# Peripherals.net
KiCad netlist of a schematic drawn in Altium Designer
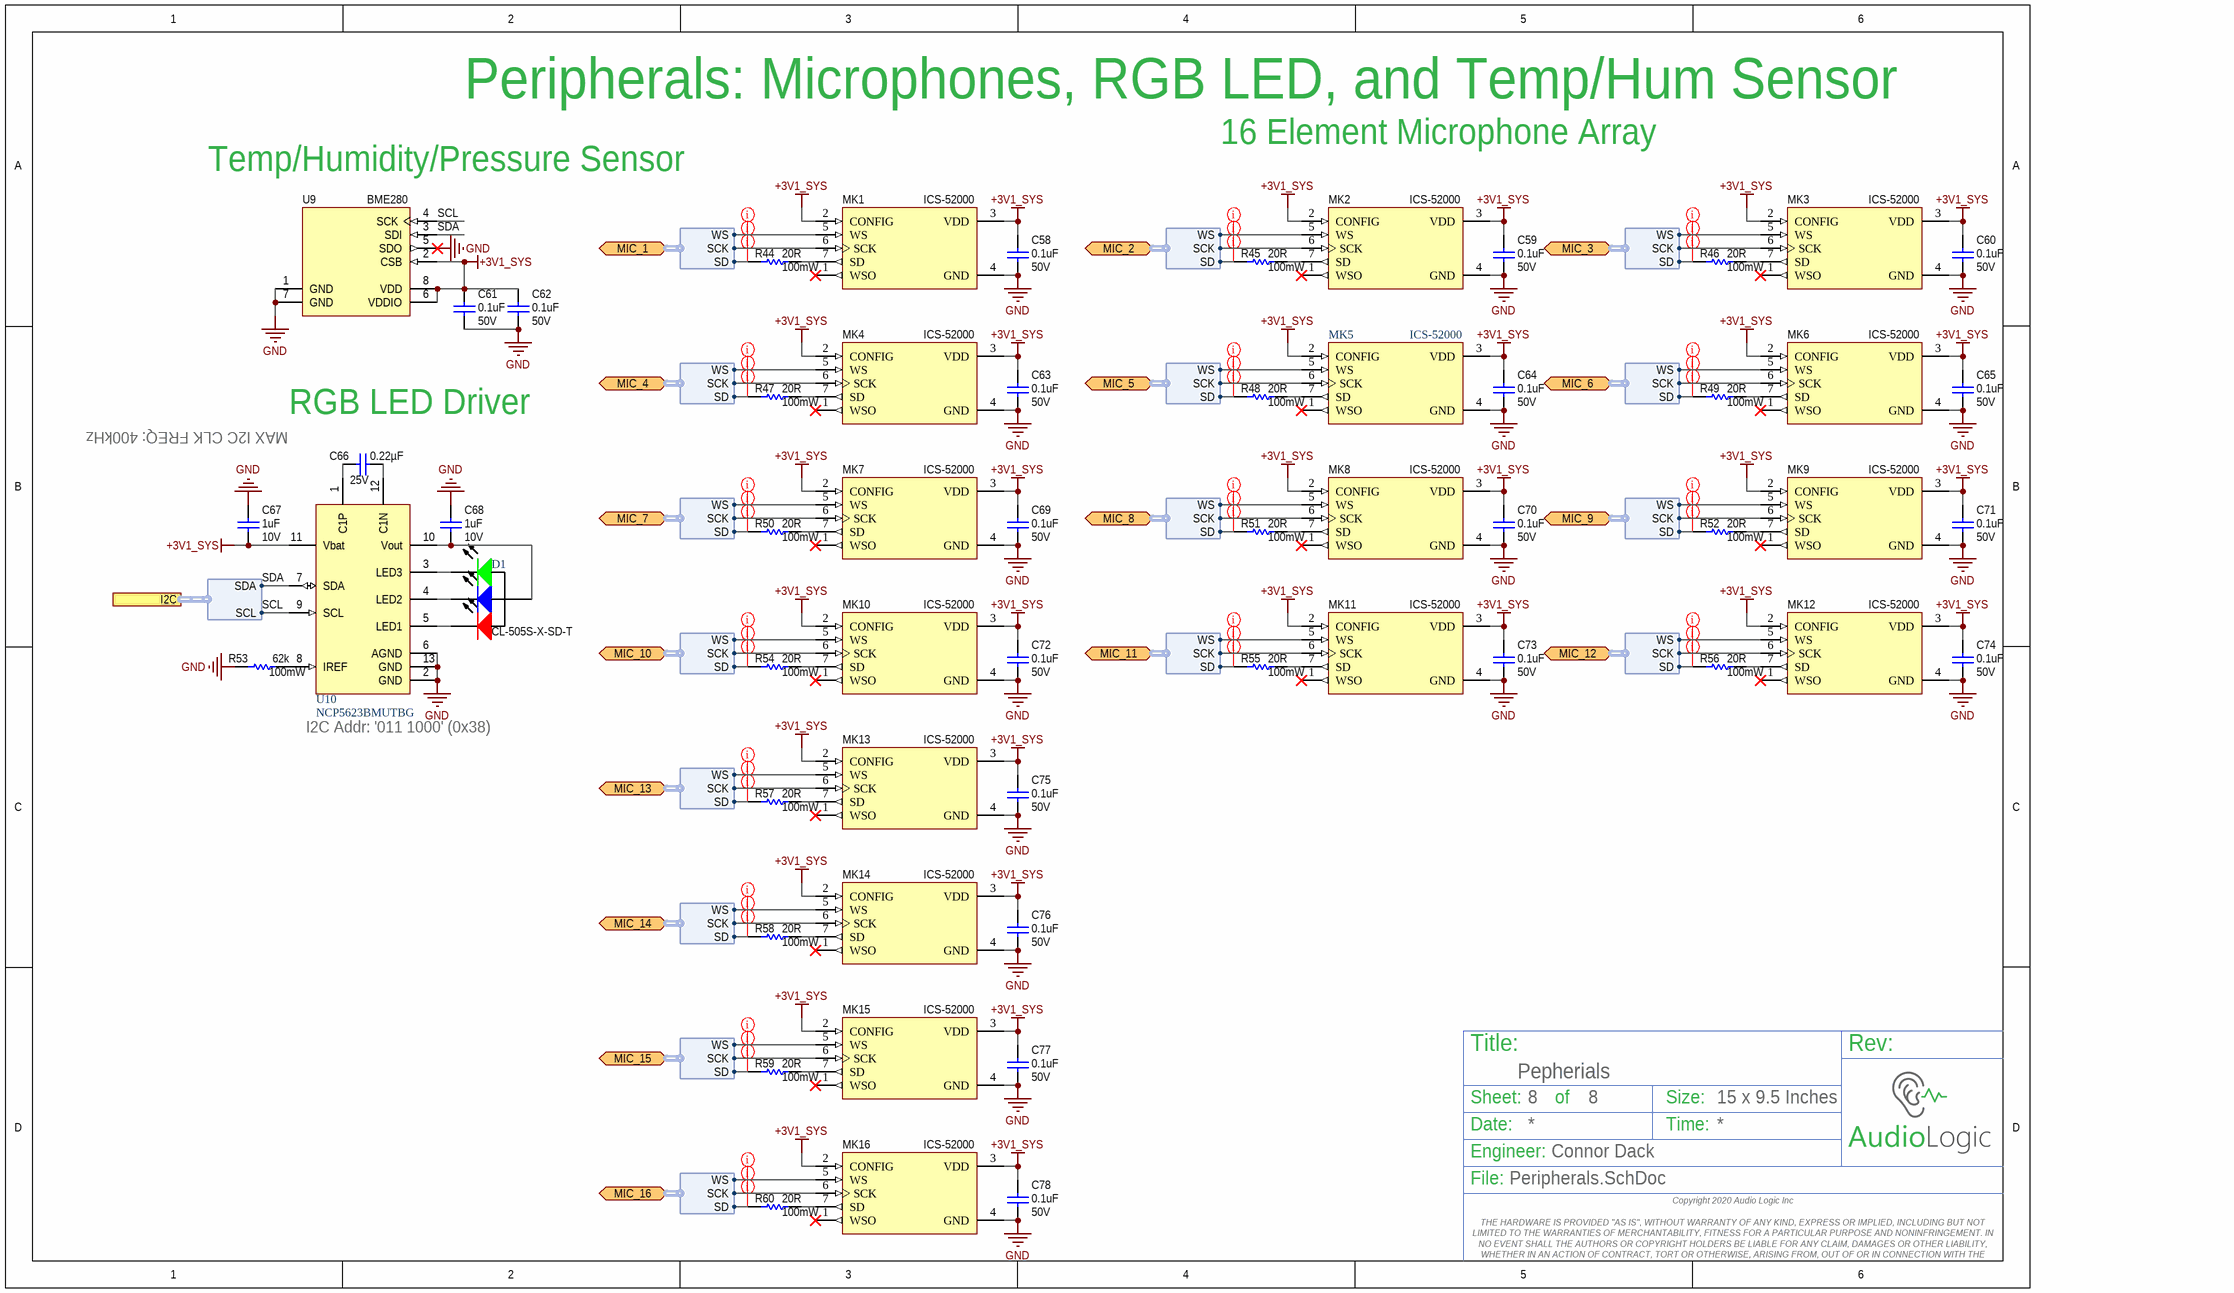
[diagram p0: Peripherals.SchDoc]

(export (version "E")
  (design (tool "Eeschema 10.0.6"))
  (components
    (comp (ref "C58")
      (value "UMK105B7104KVHF")
      (footprint "2-0402_L")
      (description "CAP CER 0.1uF 50V X7R +/-10% 0402 AEC-Q200")
      (fields
        (field (name "MANUFACTURER") "Taiyo Yuden")
        (field (name "TOLERANCE") "10%")
        (field (name "CAPACITANCE") "0.1uF")
        (field (name "VOLTAGE RATING") "50V")
      )
      (libsource (lib "Schematic_Components") (part "UMK105B7104KVHF"))
    )
    (comp (ref "C59")
      (value "UMK105B7104KVHF")
      (footprint "2-0402_L")
      (description "CAP CER 0.1uF 50V X7R +/-10% 0402 AEC-Q200")
      (fields
        (field (name "MANUFACTURER") "Taiyo Yuden")
        (field (name "TOLERANCE") "10%")
        (field (name "CAPACITANCE") "0.1uF")
        (field (name "VOLTAGE RATING") "50V")
      )
      (libsource (lib "Schematic_Components") (part "UMK105B7104KVHF"))
    )
    (comp (ref "C60")
      (value "UMK105B7104KVHF")
      (footprint "2-0402_L")
      (description "CAP CER 0.1uF 50V X7R +/-10% 0402 AEC-Q200")
      (fields
        (field (name "MANUFACTURER") "Taiyo Yuden")
        (field (name "TOLERANCE") "10%")
        (field (name "CAPACITANCE") "0.1uF")
        (field (name "VOLTAGE RATING") "50V")
      )
      (libsource (lib "Schematic_Components") (part "UMK105B7104KVHF"))
    )
    (comp (ref "C61")
      (value "UMK105B7104KVHF")
      (footprint "2-0402_L")
      (description "CAP CER 0.1uF 50V X7R +/-10% 0402 AEC-Q200")
      (fields
        (field (name "MANUFACTURER") "Taiyo Yuden")
        (field (name "TOLERANCE") "10%")
        (field (name "CAPACITANCE") "0.1uF")
        (field (name "VOLTAGE RATING") "50V")
      )
      (libsource (lib "Schematic_Components") (part "UMK105B7104KVHF"))
    )
    (comp (ref "C62")
      (value "UMK105B7104KVHF")
      (footprint "2-0402_L")
      (description "CAP CER 0.1uF 50V X7R +/-10% 0402 AEC-Q200")
      (fields
        (field (name "MANUFACTURER") "Taiyo Yuden")
        (field (name "TOLERANCE") "10%")
        (field (name "CAPACITANCE") "0.1uF")
        (field (name "VOLTAGE RATING") "50V")
      )
      (libsource (lib "Schematic_Components") (part "UMK105B7104KVHF"))
    )
    (comp (ref "C63")
      (value "UMK105B7104KVHF")
      (footprint "2-0402_L")
      (description "CAP CER 0.1uF 50V X7R +/-10% 0402 AEC-Q200")
      (fields
        (field (name "MANUFACTURER") "Taiyo Yuden")
        (field (name "TOLERANCE") "10%")
        (field (name "CAPACITANCE") "0.1uF")
        (field (name "VOLTAGE RATING") "50V")
      )
      (libsource (lib "Schematic_Components") (part "UMK105B7104KVHF"))
    )
    (comp (ref "C64")
      (value "UMK105B7104KVHF")
      (footprint "2-0402_L")
      (description "CAP CER 0.1uF 50V X7R +/-10% 0402 AEC-Q200")
      (fields
        (field (name "MANUFACTURER") "Taiyo Yuden")
        (field (name "TOLERANCE") "10%")
        (field (name "CAPACITANCE") "0.1uF")
        (field (name "VOLTAGE RATING") "50V")
      )
      (libsource (lib "Schematic_Components") (part "UMK105B7104KVHF"))
    )
    (comp (ref "C65")
      (value "UMK105B7104KVHF")
      (footprint "2-0402_L")
      (description "CAP CER 0.1uF 50V X7R +/-10% 0402 AEC-Q200")
      (fields
        (field (name "MANUFACTURER") "Taiyo Yuden")
        (field (name "TOLERANCE") "10%")
        (field (name "CAPACITANCE") "0.1uF")
        (field (name "VOLTAGE RATING") "50V")
      )
      (libsource (lib "Schematic_Components") (part "UMK105B7104KVHF"))
    )
    (comp (ref "C66")
      (value "C1005X7R1E224K050BB")
      (footprint "2-0402_L")
      (description "CAP CER 0.22UF 25V X7R 0402")
      (fields
        (field (name "MANUFACTURER") "TDK Corporation")
        (field (name "TOLERANCE") "±10%")
        (field (name "VOLTAGE - RATED") "25V")
        (field (name "CAPACITANCE") "0.22µF")
      )
      (libsource (lib "Schematic_Components") (part "C1005X7R1E224K050BB"))
    )
    (comp (ref "C67")
      (value "CGB2A1X5R1A105K033BC")
      (footprint "2-0402_L")
      (description "CAP CER 1UF 10V X5R 0402")
      (fields
        (field (name "MANUFACTURER") "TDK")
        (field (name "TOLERANCE") "10%")
        (field (name "VOLTAGE RATING") "10V")
        (field (name "CAPACITANCE") "1uF")
      )
      (libsource (lib "Schematic_Components") (part "CGB2A1X5R1A105K033BC"))
    )
    (comp (ref "C68")
      (value "CGB2A1X5R1A105K033BC")
      (footprint "2-0402_L")
      (description "CAP CER 1UF 10V X5R 0402")
      (fields
        (field (name "MANUFACTURER") "TDK")
        (field (name "TOLERANCE") "10%")
        (field (name "VOLTAGE RATING") "10V")
        (field (name "CAPACITANCE") "1uF")
      )
      (libsource (lib "Schematic_Components") (part "CGB2A1X5R1A105K033BC"))
    )
    (comp (ref "C69")
      (value "UMK105B7104KVHF")
      (footprint "2-0402_L")
      (description "CAP CER 0.1uF 50V X7R +/-10% 0402 AEC-Q200")
      (fields
        (field (name "MANUFACTURER") "Taiyo Yuden")
        (field (name "TOLERANCE") "10%")
        (field (name "CAPACITANCE") "0.1uF")
        (field (name "VOLTAGE RATING") "50V")
      )
      (libsource (lib "Schematic_Components") (part "UMK105B7104KVHF"))
    )
    (comp (ref "C70")
      (value "UMK105B7104KVHF")
      (footprint "2-0402_L")
      (description "CAP CER 0.1uF 50V X7R +/-10% 0402 AEC-Q200")
      (fields
        (field (name "MANUFACTURER") "Taiyo Yuden")
        (field (name "TOLERANCE") "10%")
        (field (name "CAPACITANCE") "0.1uF")
        (field (name "VOLTAGE RATING") "50V")
      )
      (libsource (lib "Schematic_Components") (part "UMK105B7104KVHF"))
    )
    (comp (ref "C71")
      (value "UMK105B7104KVHF")
      (footprint "2-0402_L")
      (description "CAP CER 0.1uF 50V X7R +/-10% 0402 AEC-Q200")
      (fields
        (field (name "MANUFACTURER") "Taiyo Yuden")
        (field (name "TOLERANCE") "10%")
        (field (name "CAPACITANCE") "0.1uF")
        (field (name "VOLTAGE RATING") "50V")
      )
      (libsource (lib "Schematic_Components") (part "UMK105B7104KVHF"))
    )
    (comp (ref "C72")
      (value "UMK105B7104KVHF")
      (footprint "2-0402_L")
      (description "CAP CER 0.1uF 50V X7R +/-10% 0402 AEC-Q200")
      (fields
        (field (name "MANUFACTURER") "Taiyo Yuden")
        (field (name "TOLERANCE") "10%")
        (field (name "CAPACITANCE") "0.1uF")
        (field (name "VOLTAGE RATING") "50V")
      )
      (libsource (lib "Schematic_Components") (part "UMK105B7104KVHF"))
    )
    (comp (ref "C73")
      (value "UMK105B7104KVHF")
      (footprint "2-0402_L")
      (description "CAP CER 0.1uF 50V X7R +/-10% 0402 AEC-Q200")
      (fields
        (field (name "MANUFACTURER") "Taiyo Yuden")
        (field (name "TOLERANCE") "10%")
        (field (name "CAPACITANCE") "0.1uF")
        (field (name "VOLTAGE RATING") "50V")
      )
      (libsource (lib "Schematic_Components") (part "UMK105B7104KVHF"))
    )
    (comp (ref "C74")
      (value "UMK105B7104KVHF")
      (footprint "2-0402_L")
      (description "CAP CER 0.1uF 50V X7R +/-10% 0402 AEC-Q200")
      (fields
        (field (name "MANUFACTURER") "Taiyo Yuden")
        (field (name "TOLERANCE") "10%")
        (field (name "CAPACITANCE") "0.1uF")
        (field (name "VOLTAGE RATING") "50V")
      )
      (libsource (lib "Schematic_Components") (part "UMK105B7104KVHF"))
    )
    (comp (ref "C75")
      (value "UMK105B7104KVHF")
      (footprint "2-0402_L")
      (description "CAP CER 0.1uF 50V X7R +/-10% 0402 AEC-Q200")
      (fields
        (field (name "MANUFACTURER") "Taiyo Yuden")
        (field (name "TOLERANCE") "10%")
        (field (name "CAPACITANCE") "0.1uF")
        (field (name "VOLTAGE RATING") "50V")
      )
      (libsource (lib "Schematic_Components") (part "UMK105B7104KVHF"))
    )
    (comp (ref "C76")
      (value "UMK105B7104KVHF")
      (footprint "2-0402_L")
      (description "CAP CER 0.1uF 50V X7R +/-10% 0402 AEC-Q200")
      (fields
        (field (name "MANUFACTURER") "Taiyo Yuden")
        (field (name "TOLERANCE") "10%")
        (field (name "CAPACITANCE") "0.1uF")
        (field (name "VOLTAGE RATING") "50V")
      )
      (libsource (lib "Schematic_Components") (part "UMK105B7104KVHF"))
    )
    (comp (ref "C77")
      (value "UMK105B7104KVHF")
      (footprint "2-0402_L")
      (description "CAP CER 0.1uF 50V X7R +/-10% 0402 AEC-Q200")
      (fields
        (field (name "MANUFACTURER") "Taiyo Yuden")
        (field (name "TOLERANCE") "10%")
        (field (name "CAPACITANCE") "0.1uF")
        (field (name "VOLTAGE RATING") "50V")
      )
      (libsource (lib "Schematic_Components") (part "UMK105B7104KVHF"))
    )
    (comp (ref "C78")
      (value "UMK105B7104KVHF")
      (footprint "2-0402_L")
      (description "CAP CER 0.1uF 50V X7R +/-10% 0402 AEC-Q200")
      (fields
        (field (name "MANUFACTURER") "Taiyo Yuden")
        (field (name "TOLERANCE") "10%")
        (field (name "CAPACITANCE") "0.1uF")
        (field (name "VOLTAGE RATING") "50V")
      )
      (libsource (lib "Schematic_Components") (part "UMK105B7104KVHF"))
    )
    (comp (ref "D1")
      (value "LED TRI TOP FIRING 1.0 X 1.0")
      (footprint "CL-505S")
      (fields
        (field (name "MANUFACTURER") "Citizen")
        (field (name "MANUFACTURER PART NUMBER") "CL-505S-X-SD-T")
      )
      (libsource (lib "Schematic_Components_CD") (part "CL-505S-X-SD-T"))
    )
    (comp (ref "MK1")
      (value "ICS-52000")
      (footprint "MIC_ICS-52000")
      (description "MIC MEMS DIGITAL OMNI -26DB")
      (fields (field (name "MANUFACTURER") "TDK InvenSense"))
      (libsource (lib "Schematic_Components_CD") (part "ICS-52000"))
    )
    (comp (ref "MK2")
      (value "ICS-52000")
      (footprint "MIC_ICS-52000")
      (description "MIC MEMS DIGITAL OMNI -26DB")
      (fields (field (name "MANUFACTURER") "TDK InvenSense"))
      (libsource (lib "Schematic_Components_CD") (part "ICS-52000"))
    )
    (comp (ref "MK3")
      (value "ICS-52000")
      (footprint "MIC_ICS-52000")
      (description "MIC MEMS DIGITAL OMNI -26DB")
      (fields (field (name "MANUFACTURER") "TDK InvenSense"))
      (libsource (lib "Schematic_Components_CD") (part "ICS-52000"))
    )
    (comp (ref "MK4")
      (value "ICS-52000")
      (footprint "MIC_ICS-52000")
      (description "MIC MEMS DIGITAL OMNI -26DB")
      (fields (field (name "MANUFACTURER") "TDK InvenSense"))
      (libsource (lib "Schematic_Components_CD") (part "ICS-52000"))
    )
    (comp (ref "MK5")
      (value "ICS-52000")
      (footprint "MIC_ICS-52000")
      (description "MIC MEMS DIGITAL OMNI -26DB")
      (fields (field (name "MANUFACTURER") "TDK InvenSense"))
      (libsource (lib "Schematic_Components_CD") (part "ICS-52000"))
    )
    (comp (ref "MK6")
      (value "ICS-52000")
      (footprint "MIC_ICS-52000")
      (description "MIC MEMS DIGITAL OMNI -26DB")
      (fields (field (name "MANUFACTURER") "TDK InvenSense"))
      (libsource (lib "Schematic_Components_CD") (part "ICS-52000"))
    )
    (comp (ref "MK7")
      (value "ICS-52000")
      (footprint "MIC_ICS-52000")
      (description "MIC MEMS DIGITAL OMNI -26DB")
      (fields (field (name "MANUFACTURER") "TDK InvenSense"))
      (libsource (lib "Schematic_Components_CD") (part "ICS-52000"))
    )
    (comp (ref "MK8")
      (value "ICS-52000")
      (footprint "MIC_ICS-52000")
      (description "MIC MEMS DIGITAL OMNI -26DB")
      (fields (field (name "MANUFACTURER") "TDK InvenSense"))
      (libsource (lib "Schematic_Components_CD") (part "ICS-52000"))
    )
    (comp (ref "MK9")
      (value "ICS-52000")
      (footprint "MIC_ICS-52000")
      (description "MIC MEMS DIGITAL OMNI -26DB")
      (fields (field (name "MANUFACTURER") "TDK InvenSense"))
      (libsource (lib "Schematic_Components_CD") (part "ICS-52000"))
    )
    (comp (ref "MK10")
      (value "ICS-52000")
      (footprint "MIC_ICS-52000")
      (description "MIC MEMS DIGITAL OMNI -26DB")
      (fields (field (name "MANUFACTURER") "TDK InvenSense"))
      (libsource (lib "Schematic_Components_CD") (part "ICS-52000"))
    )
    (comp (ref "MK11")
      (value "ICS-52000")
      (footprint "MIC_ICS-52000")
      (description "MIC MEMS DIGITAL OMNI -26DB")
      (fields (field (name "MANUFACTURER") "TDK InvenSense"))
      (libsource (lib "Schematic_Components_CD") (part "ICS-52000"))
    )
    (comp (ref "MK12")
      (value "ICS-52000")
      (footprint "MIC_ICS-52000")
      (description "MIC MEMS DIGITAL OMNI -26DB")
      (fields (field (name "MANUFACTURER") "TDK InvenSense"))
      (libsource (lib "Schematic_Components_CD") (part "ICS-52000"))
    )
    (comp (ref "MK13")
      (value "ICS-52000")
      (footprint "MIC_ICS-52000")
      (description "MIC MEMS DIGITAL OMNI -26DB")
      (fields (field (name "MANUFACTURER") "TDK InvenSense"))
      (libsource (lib "Schematic_Components_CD") (part "ICS-52000"))
    )
    (comp (ref "MK14")
      (value "ICS-52000")
      (footprint "MIC_ICS-52000")
      (description "MIC MEMS DIGITAL OMNI -26DB")
      (fields (field (name "MANUFACTURER") "TDK InvenSense"))
      (libsource (lib "Schematic_Components_CD") (part "ICS-52000"))
    )
    (comp (ref "MK15")
      (value "ICS-52000")
      (footprint "MIC_ICS-52000")
      (description "MIC MEMS DIGITAL OMNI -26DB")
      (fields (field (name "MANUFACTURER") "TDK InvenSense"))
      (libsource (lib "Schematic_Components_CD") (part "ICS-52000"))
    )
    (comp (ref "MK16")
      (value "ICS-52000")
      (footprint "MIC_ICS-52000")
      (description "MIC MEMS DIGITAL OMNI -26DB")
      (fields (field (name "MANUFACTURER") "TDK InvenSense"))
      (libsource (lib "Schematic_Components_CD") (part "ICS-52000"))
    )
    (comp (ref "R44")
      (value "ERJ-2RKF20R0X")
      (footprint "RESC1005X40X25LL05T05")
      (description "RES SMD 20 OHM 1% 1/10W 0402")
      (fields
        (field (name "MANUFACTURER") "Panasonic")
        (field (name "RESISTANCE") "20R")
        (field (name "POWER RATING") "100mW")
        (field (name "TOLERANCE") "1%")
      )
      (libsource (lib "Altium Content Vault") (part "RES"))
    )
    (comp (ref "R45")
      (value "ERJ-2RKF20R0X")
      (footprint "RESC1005X40X25LL05T05")
      (description "RES SMD 20 OHM 1% 1/10W 0402")
      (fields
        (field (name "MANUFACTURER") "Panasonic")
        (field (name "RESISTANCE") "20R")
        (field (name "POWER RATING") "100mW")
        (field (name "TOLERANCE") "1%")
      )
      (libsource (lib "Altium Content Vault") (part "RES"))
    )
    (comp (ref "R46")
      (value "ERJ-2RKF20R0X")
      (footprint "RESC1005X40X25LL05T05")
      (description "RES SMD 20 OHM 1% 1/10W 0402")
      (fields
        (field (name "MANUFACTURER") "Panasonic")
        (field (name "RESISTANCE") "20R")
        (field (name "POWER RATING") "100mW")
        (field (name "TOLERANCE") "1%")
      )
      (libsource (lib "Altium Content Vault") (part "RES"))
    )
    (comp (ref "R47")
      (value "ERJ-2RKF20R0X")
      (footprint "RESC1005X40X25LL05T05")
      (description "RES SMD 20 OHM 1% 1/10W 0402")
      (fields
        (field (name "MANUFACTURER") "Panasonic")
        (field (name "RESISTANCE") "20R")
        (field (name "POWER RATING") "100mW")
        (field (name "TOLERANCE") "1%")
      )
      (libsource (lib "Altium Content Vault") (part "RES"))
    )
    (comp (ref "R48")
      (value "ERJ-2RKF20R0X")
      (footprint "RESC1005X40X25LL05T05")
      (description "RES SMD 20 OHM 1% 1/10W 0402")
      (fields
        (field (name "MANUFACTURER") "Panasonic")
        (field (name "RESISTANCE") "20R")
        (field (name "POWER RATING") "100mW")
        (field (name "TOLERANCE") "1%")
      )
      (libsource (lib "Altium Content Vault") (part "RES"))
    )
    (comp (ref "R49")
      (value "ERJ-2RKF20R0X")
      (footprint "RESC1005X40X25LL05T05")
      (description "RES SMD 20 OHM 1% 1/10W 0402")
      (fields
        (field (name "MANUFACTURER") "Panasonic")
        (field (name "RESISTANCE") "20R")
        (field (name "POWER RATING") "100mW")
        (field (name "TOLERANCE") "1%")
      )
      (libsource (lib "Altium Content Vault") (part "RES"))
    )
    (comp (ref "R50")
      (value "ERJ-2RKF20R0X")
      (footprint "RESC1005X40X25LL05T05")
      (description "RES SMD 20 OHM 1% 1/10W 0402")
      (fields
        (field (name "MANUFACTURER") "Panasonic")
        (field (name "RESISTANCE") "20R")
        (field (name "POWER RATING") "100mW")
        (field (name "TOLERANCE") "1%")
      )
      (libsource (lib "Altium Content Vault") (part "RES"))
    )
    (comp (ref "R51")
      (value "ERJ-2RKF20R0X")
      (footprint "RESC1005X40X25LL05T05")
      (description "RES SMD 20 OHM 1% 1/10W 0402")
      (fields
        (field (name "MANUFACTURER") "Panasonic")
        (field (name "RESISTANCE") "20R")
        (field (name "POWER RATING") "100mW")
        (field (name "TOLERANCE") "1%")
      )
      (libsource (lib "Altium Content Vault") (part "RES"))
    )
    (comp (ref "R52")
      (value "ERJ-2RKF20R0X")
      (footprint "RESC1005X40X25LL05T05")
      (description "RES SMD 20 OHM 1% 1/10W 0402")
      (fields
        (field (name "MANUFACTURER") "Panasonic")
        (field (name "RESISTANCE") "20R")
        (field (name "POWER RATING") "100mW")
        (field (name "TOLERANCE") "1%")
      )
      (libsource (lib "Altium Content Vault") (part "RES"))
    )
    (comp (ref "R53")
      (value "ERJ-2GEJ623X")
      (footprint "2-0402_R_L")
      (description "RES SMD 62K OHM 5% 1/10W 0402")
      (fields
        (field (name "MANUFACTURER") "Panasonic Electronic Components")
        (field (name "TOLERANCE") "±5%")
        (field (name "POWER (WATTS)") "100mW")
        (field (name "RESISTANCE (OHMS)") "62k")
      )
      (libsource (lib "Schematic_Components") (part "ERJ-2GEJ623X"))
    )
    (comp (ref "R54")
      (value "ERJ-2RKF20R0X")
      (footprint "RESC1005X40X25LL05T05")
      (description "RES SMD 20 OHM 1% 1/10W 0402")
      (fields
        (field (name "MANUFACTURER") "Panasonic")
        (field (name "RESISTANCE") "20R")
        (field (name "POWER RATING") "100mW")
        (field (name "TOLERANCE") "1%")
      )
      (libsource (lib "Altium Content Vault") (part "RES"))
    )
    (comp (ref "R55")
      (value "ERJ-2RKF20R0X")
      (footprint "RESC1005X40X25LL05T05")
      (description "RES SMD 20 OHM 1% 1/10W 0402")
      (fields
        (field (name "MANUFACTURER") "Panasonic")
        (field (name "RESISTANCE") "20R")
        (field (name "POWER RATING") "100mW")
        (field (name "TOLERANCE") "1%")
      )
      (libsource (lib "Altium Content Vault") (part "RES"))
    )
    (comp (ref "R56")
      (value "ERJ-2RKF20R0X")
      (footprint "RESC1005X40X25LL05T05")
      (description "RES SMD 20 OHM 1% 1/10W 0402")
      (fields
        (field (name "MANUFACTURER") "Panasonic")
        (field (name "RESISTANCE") "20R")
        (field (name "POWER RATING") "100mW")
        (field (name "TOLERANCE") "1%")
      )
      (libsource (lib "Altium Content Vault") (part "RES"))
    )
    (comp (ref "R57")
      (value "ERJ-2RKF20R0X")
      (footprint "RESC1005X40X25LL05T05")
      (description "RES SMD 20 OHM 1% 1/10W 0402")
      (fields
        (field (name "MANUFACTURER") "Panasonic")
        (field (name "RESISTANCE") "20R")
        (field (name "POWER RATING") "100mW")
        (field (name "TOLERANCE") "1%")
      )
      (libsource (lib "Altium Content Vault") (part "RES"))
    )
    (comp (ref "R58")
      (value "ERJ-2RKF20R0X")
      (footprint "RESC1005X40X25LL05T05")
      (description "RES SMD 20 OHM 1% 1/10W 0402")
      (fields
        (field (name "MANUFACTURER") "Panasonic")
        (field (name "RESISTANCE") "20R")
        (field (name "POWER RATING") "100mW")
        (field (name "TOLERANCE") "1%")
      )
      (libsource (lib "Altium Content Vault") (part "RES"))
    )
    (comp (ref "R59")
      (value "ERJ-2RKF20R0X")
      (footprint "RESC1005X40X25LL05T05")
      (description "RES SMD 20 OHM 1% 1/10W 0402")
      (fields
        (field (name "MANUFACTURER") "Panasonic")
        (field (name "RESISTANCE") "20R")
        (field (name "POWER RATING") "100mW")
        (field (name "TOLERANCE") "1%")
      )
      (libsource (lib "Altium Content Vault") (part "RES"))
    )
    (comp (ref "R60")
      (value "ERJ-2RKF20R0X")
      (footprint "RESC1005X40X25LL05T05")
      (description "RES SMD 20 OHM 1% 1/10W 0402")
      (fields
        (field (name "MANUFACTURER") "Panasonic")
        (field (name "RESISTANCE") "20R")
        (field (name "POWER RATING") "100mW")
        (field (name "TOLERANCE") "1%")
      )
      (libsource (lib "Altium Content Vault") (part "RES"))
    )
    (comp (ref "U9")
      (value "BME280")
      (footprint "BOSC-BME280-8_V")
      (fields (field (name "MANUFACTURER") "Bosch Sensortec"))
      (libsource (lib "Altium Content Vault") (part "BOSC-BME280-8"))
    )
    (comp (ref "U10")
      (value "IC LED DRIVER RGLTR 30MA 12LLGA")
      (footprint "513AA")
      (description "LED Driver IC 3 Output DC DC Regulator Switched Capacitor (Charge Pump) 30mA 12-LLGA (2x2)")
      (fields
        (field (name "MANUFACTURER") "ON Semiconductor")
        (field (name "MANUFACTURER PART NUMBER") "NCP5623BMUTBG")
      )
      (libsource (lib "Schematic_Components_CD") (part "NCP5623BMUTBG"))
    )
  )
  (nets
    (net (code "18") (name "+3V1_SYS") (class "Default")
      (node (ref "C58") (pin "2") (pinfunction "2_2") (pintype "passive"))
      (node (ref "C59") (pin "2") (pinfunction "2_2") (pintype "passive"))
      (node (ref "C60") (pin "2") (pinfunction "2_2") (pintype "passive"))
      (node (ref "C61") (pin "2") (pinfunction "2_2") (pintype "passive"))
      (node (ref "C62") (pin "2") (pinfunction "2_2") (pintype "passive"))
      (node (ref "C63") (pin "2") (pinfunction "2_2") (pintype "passive"))
      (node (ref "C64") (pin "2") (pinfunction "2_2") (pintype "passive"))
      (node (ref "C65") (pin "2") (pinfunction "2_2") (pintype "passive"))
      (node (ref "C67") (pin "2") (pinfunction "2_2") (pintype "passive"))
      (node (ref "C69") (pin "2") (pinfunction "2_2") (pintype "passive"))
      (node (ref "C70") (pin "2") (pinfunction "2_2") (pintype "passive"))
      (node (ref "C71") (pin "2") (pinfunction "2_2") (pintype "passive"))
      (node (ref "C72") (pin "2") (pinfunction "2_2") (pintype "passive"))
      (node (ref "C73") (pin "2") (pinfunction "2_2") (pintype "passive"))
      (node (ref "C74") (pin "2") (pinfunction "2_2") (pintype "passive"))
      (node (ref "C75") (pin "2") (pinfunction "2_2") (pintype "passive"))
      (node (ref "C76") (pin "2") (pinfunction "2_2") (pintype "passive"))
      (node (ref "C77") (pin "2") (pinfunction "2_2") (pintype "passive"))
      (node (ref "C78") (pin "2") (pinfunction "2_2") (pintype "passive"))
      (node (ref "MK1") (pin "2") (pinfunction "CONFIG_2") (pintype "input"))
      (node (ref "MK1") (pin "3") (pinfunction "VDD_3") (pintype "power_in"))
      (node (ref "MK10") (pin "2") (pinfunction "CONFIG_2") (pintype "input"))
      (node (ref "MK10") (pin "3") (pinfunction "VDD_3") (pintype "power_in"))
      (node (ref "MK11") (pin "2") (pinfunction "CONFIG_2") (pintype "input"))
      (node (ref "MK11") (pin "3") (pinfunction "VDD_3") (pintype "power_in"))
      (node (ref "MK12") (pin "2") (pinfunction "CONFIG_2") (pintype "input"))
      (node (ref "MK12") (pin "3") (pinfunction "VDD_3") (pintype "power_in"))
      (node (ref "MK13") (pin "2") (pinfunction "CONFIG_2") (pintype "input"))
      (node (ref "MK13") (pin "3") (pinfunction "VDD_3") (pintype "power_in"))
      (node (ref "MK14") (pin "2") (pinfunction "CONFIG_2") (pintype "input"))
      (node (ref "MK14") (pin "3") (pinfunction "VDD_3") (pintype "power_in"))
      (node (ref "MK15") (pin "2") (pinfunction "CONFIG_2") (pintype "input"))
      (node (ref "MK15") (pin "3") (pinfunction "VDD_3") (pintype "power_in"))
      (node (ref "MK16") (pin "2") (pinfunction "CONFIG_2") (pintype "input"))
      (node (ref "MK16") (pin "3") (pinfunction "VDD_3") (pintype "power_in"))
      (node (ref "MK2") (pin "2") (pinfunction "CONFIG_2") (pintype "input"))
      (node (ref "MK2") (pin "3") (pinfunction "VDD_3") (pintype "power_in"))
      (node (ref "MK3") (pin "2") (pinfunction "CONFIG_2") (pintype "input"))
      (node (ref "MK3") (pin "3") (pinfunction "VDD_3") (pintype "power_in"))
      (node (ref "MK4") (pin "2") (pinfunction "CONFIG_2") (pintype "input"))
      (node (ref "MK4") (pin "3") (pinfunction "VDD_3") (pintype "power_in"))
      (node (ref "MK5") (pin "2") (pinfunction "CONFIG_2") (pintype "input"))
      (node (ref "MK5") (pin "3") (pinfunction "VDD_3") (pintype "power_in"))
      (node (ref "MK6") (pin "2") (pinfunction "CONFIG_2") (pintype "input"))
      (node (ref "MK6") (pin "3") (pinfunction "VDD_3") (pintype "power_in"))
      (node (ref "MK7") (pin "2") (pinfunction "CONFIG_2") (pintype "input"))
      (node (ref "MK7") (pin "3") (pinfunction "VDD_3") (pintype "power_in"))
      (node (ref "MK8") (pin "2") (pinfunction "CONFIG_2") (pintype "input"))
      (node (ref "MK8") (pin "3") (pinfunction "VDD_3") (pintype "power_in"))
      (node (ref "MK9") (pin "2") (pinfunction "CONFIG_2") (pintype "input"))
      (node (ref "MK9") (pin "3") (pinfunction "VDD_3") (pintype "power_in"))
      (node (ref "U10") (pin "11") (pinfunction "Vbat_11") (pintype "power_in"))
      (node (ref "U9") (pin "2") (pinfunction "CSB_2") (pintype "input"))
      (node (ref "U9") (pin "6") (pinfunction "VDDIO_6") (pintype "power_in"))
      (node (ref "U9") (pin "8") (pinfunction "VDD_8") (pintype "power_in"))
    )
    (net (code "19") (name "/SCL") (class "Default")
      (node (ref "U10") (pin "9") (pinfunction "SCL_9") (pintype "input"))
      (node (ref "U9") (pin "4") (pinfunction "SCK_4") (pintype "input"))
    )
    (net (code "20") (name "/SDA") (class "Default")
      (node (ref "U10") (pin "7") (pinfunction "SDA_7") (pintype "bidirectional"))
      (node (ref "U9") (pin "3") (pinfunction "SDI_3") (pintype "input"))
    )
    (net (code "38") (name "GND") (class "Default")
      (node (ref "C58") (pin "1") (pinfunction "1_1") (pintype "passive"))
      (node (ref "C59") (pin "1") (pinfunction "1_1") (pintype "passive"))
      (node (ref "C60") (pin "1") (pinfunction "1_1") (pintype "passive"))
      (node (ref "C61") (pin "1") (pinfunction "1_1") (pintype "passive"))
      (node (ref "C62") (pin "1") (pinfunction "1_1") (pintype "passive"))
      (node (ref "C63") (pin "1") (pinfunction "1_1") (pintype "passive"))
      (node (ref "C64") (pin "1") (pinfunction "1_1") (pintype "passive"))
      (node (ref "C65") (pin "1") (pinfunction "1_1") (pintype "passive"))
      (node (ref "C67") (pin "1") (pinfunction "1_1") (pintype "passive"))
      (node (ref "C68") (pin "2") (pinfunction "2_2") (pintype "passive"))
      (node (ref "C69") (pin "1") (pinfunction "1_1") (pintype "passive"))
      (node (ref "C70") (pin "1") (pinfunction "1_1") (pintype "passive"))
      (node (ref "C71") (pin "1") (pinfunction "1_1") (pintype "passive"))
      (node (ref "C72") (pin "1") (pinfunction "1_1") (pintype "passive"))
      (node (ref "C73") (pin "1") (pinfunction "1_1") (pintype "passive"))
      (node (ref "C74") (pin "1") (pinfunction "1_1") (pintype "passive"))
      (node (ref "C75") (pin "1") (pinfunction "1_1") (pintype "passive"))
      (node (ref "C76") (pin "1") (pinfunction "1_1") (pintype "passive"))
      (node (ref "C77") (pin "1") (pinfunction "1_1") (pintype "passive"))
      (node (ref "C78") (pin "1") (pinfunction "1_1") (pintype "passive"))
      (node (ref "MK1") (pin "4") (pinfunction "GND_4") (pintype "power_in"))
      (node (ref "MK10") (pin "4") (pinfunction "GND_4") (pintype "power_in"))
      (node (ref "MK11") (pin "4") (pinfunction "GND_4") (pintype "power_in"))
      (node (ref "MK12") (pin "4") (pinfunction "GND_4") (pintype "power_in"))
      (node (ref "MK13") (pin "4") (pinfunction "GND_4") (pintype "power_in"))
      (node (ref "MK14") (pin "4") (pinfunction "GND_4") (pintype "power_in"))
      (node (ref "MK15") (pin "4") (pinfunction "GND_4") (pintype "power_in"))
      (node (ref "MK16") (pin "4") (pinfunction "GND_4") (pintype "power_in"))
      (node (ref "MK2") (pin "4") (pinfunction "GND_4") (pintype "power_in"))
      (node (ref "MK3") (pin "4") (pinfunction "GND_4") (pintype "power_in"))
      (node (ref "MK4") (pin "4") (pinfunction "GND_4") (pintype "power_in"))
      (node (ref "MK5") (pin "4") (pinfunction "GND_4") (pintype "power_in"))
      (node (ref "MK6") (pin "4") (pinfunction "GND_4") (pintype "power_in"))
      (node (ref "MK7") (pin "4") (pinfunction "GND_4") (pintype "power_in"))
      (node (ref "MK8") (pin "4") (pinfunction "GND_4") (pintype "power_in"))
      (node (ref "MK9") (pin "4") (pinfunction "GND_4") (pintype "power_in"))
      (node (ref "R53") (pin "1") (pinfunction "1_1") (pintype "passive"))
      (node (ref "U10") (pin "13") (pinfunction "GND_13") (pintype "passive"))
      (node (ref "U10") (pin "2") (pinfunction "GND_2") (pintype "power_in"))
      (node (ref "U10") (pin "6") (pinfunction "AGND_6") (pintype "power_in"))
      (node (ref "U9") (pin "1") (pinfunction "GND_1") (pintype "power_in"))
      (node (ref "U9") (pin "5") (pinfunction "SDO_5") (pintype "output"))
      (node (ref "U9") (pin "7") (pinfunction "GND_7") (pintype "power_in"))
    )
    (net (code "39") (name "Net-(D1-A)") (class "Default")
      (node (ref "C68") (pin "1") (pinfunction "1_1") (pintype "passive"))
      (node (ref "D1") (pin "4") (pinfunction "A_4") (pintype "passive"))
      (node (ref "U10") (pin "10") (pinfunction "Vout_10") (pintype "power_in"))
    )
    (net (code "40") (name "Net-(MK1-SD)") (class "Default")
      (node (ref "MK1") (pin "7") (pinfunction "SD_7") (pintype "output"))
      (node (ref "R44") (pin "2") (pinfunction "2_2") (pintype "passive"))
    )
    (net (code "41") (name "Net-(MK2-SD)") (class "Default")
      (node (ref "MK2") (pin "7") (pinfunction "SD_7") (pintype "output"))
      (node (ref "R45") (pin "2") (pinfunction "2_2") (pintype "passive"))
    )
    (net (code "42") (name "Net-(MK3-SD)") (class "Default")
      (node (ref "MK3") (pin "7") (pinfunction "SD_7") (pintype "output"))
      (node (ref "R46") (pin "2") (pinfunction "2_2") (pintype "passive"))
    )
    (net (code "43") (name "Net-(MK4-SD)") (class "Default")
      (node (ref "MK4") (pin "7") (pinfunction "SD_7") (pintype "output"))
      (node (ref "R47") (pin "2") (pinfunction "2_2") (pintype "passive"))
    )
    (net (code "44") (name "Net-(MK5-SD)") (class "Default")
      (node (ref "MK5") (pin "7") (pinfunction "SD_7") (pintype "output"))
      (node (ref "R48") (pin "2") (pinfunction "2_2") (pintype "passive"))
    )
    (net (code "45") (name "Net-(MK6-SD)") (class "Default")
      (node (ref "MK6") (pin "7") (pinfunction "SD_7") (pintype "output"))
      (node (ref "R49") (pin "2") (pinfunction "2_2") (pintype "passive"))
    )
    (net (code "46") (name "Net-(MK7-SD)") (class "Default")
      (node (ref "MK7") (pin "7") (pinfunction "SD_7") (pintype "output"))
      (node (ref "R50") (pin "2") (pinfunction "2_2") (pintype "passive"))
    )
    (net (code "47") (name "Net-(MK8-SD)") (class "Default")
      (node (ref "MK8") (pin "7") (pinfunction "SD_7") (pintype "output"))
      (node (ref "R51") (pin "2") (pinfunction "2_2") (pintype "passive"))
    )
    (net (code "48") (name "Net-(MK9-SD)") (class "Default")
      (node (ref "MK9") (pin "7") (pinfunction "SD_7") (pintype "output"))
      (node (ref "R52") (pin "2") (pinfunction "2_2") (pintype "passive"))
    )
    (net (code "49") (name "Net-(MK10-SD)") (class "Default")
      (node (ref "MK10") (pin "7") (pinfunction "SD_7") (pintype "output"))
      (node (ref "R54") (pin "2") (pinfunction "2_2") (pintype "passive"))
    )
    (net (code "50") (name "Net-(MK11-SD)") (class "Default")
      (node (ref "MK11") (pin "7") (pinfunction "SD_7") (pintype "output"))
      (node (ref "R55") (pin "2") (pinfunction "2_2") (pintype "passive"))
    )
    (net (code "51") (name "Net-(MK12-SD)") (class "Default")
      (node (ref "MK12") (pin "7") (pinfunction "SD_7") (pintype "output"))
      (node (ref "R56") (pin "2") (pinfunction "2_2") (pintype "passive"))
    )
    (net (code "52") (name "Net-(MK13-SD)") (class "Default")
      (node (ref "MK13") (pin "7") (pinfunction "SD_7") (pintype "output"))
      (node (ref "R57") (pin "2") (pinfunction "2_2") (pintype "passive"))
    )
    (net (code "53") (name "Net-(MK14-SD)") (class "Default")
      (node (ref "MK14") (pin "7") (pinfunction "SD_7") (pintype "output"))
      (node (ref "R58") (pin "2") (pinfunction "2_2") (pintype "passive"))
    )
    (net (code "54") (name "Net-(MK15-SD)") (class "Default")
      (node (ref "MK15") (pin "7") (pinfunction "SD_7") (pintype "output"))
      (node (ref "R59") (pin "2") (pinfunction "2_2") (pintype "passive"))
    )
    (net (code "55") (name "Net-(MK16-SD)") (class "Default")
      (node (ref "MK16") (pin "7") (pinfunction "SD_7") (pintype "output"))
      (node (ref "R60") (pin "2") (pinfunction "2_2") (pintype "passive"))
    )
    (net (code "56") (name "Net-(U10-C1N)") (class "Default")
      (node (ref "C66") (pin "2") (pinfunction "2_2") (pintype "passive"))
      (node (ref "U10") (pin "12") (pinfunction "C1N_12") (pintype "power_in"))
    )
    (net (code "57") (name "Net-(U10-C1P)") (class "Default")
      (node (ref "C66") (pin "1") (pinfunction "1_1") (pintype "passive"))
      (node (ref "U10") (pin "1") (pinfunction "C1P_1") (pintype "power_in"))
    )
    (net (code "58") (name "Net-(U10-IREF)") (class "Default")
      (node (ref "R53") (pin "2") (pinfunction "2_2") (pintype "passive"))
      (node (ref "U10") (pin "8") (pinfunction "IREF_8") (pintype "input"))
    )
    (net (code "59") (name "Net-(U10-LED1)") (class "Default")
      (node (ref "D1") (pin "2") (pinfunction "K_2") (pintype "passive"))
      (node (ref "U10") (pin "5") (pinfunction "LED1_5") (pintype "power_in"))
    )
    (net (code "60") (name "Net-(U10-LED2)") (class "Default")
      (node (ref "D1") (pin "1") (pinfunction "K_1") (pintype "passive"))
      (node (ref "U10") (pin "4") (pinfunction "LED2_4") (pintype "power_in"))
    )
    (net (code "61") (name "Net-(U10-LED3)") (class "Default")
      (node (ref "D1") (pin "3") (pinfunction "K_3") (pintype "passive"))
      (node (ref "U10") (pin "3") (pinfunction "LED3_3") (pintype "power_in"))
    )
    (net (code "62") (name "unconnected-(MK1-SCK-Pad6)") (class "Default")
      (node (ref "MK1") (pin "6") (pinfunction "SCK_6") (pintype "input"))
    )
    (net (code "63") (name "unconnected-(MK1-WS-Pad5)") (class "Default")
      (node (ref "MK1") (pin "5") (pinfunction "WS_5") (pintype "input"))
    )
    (net (code "64") (name "unconnected-(MK1-WSO-Pad1)") (class "Default")
      (node (ref "MK1") (pin "1") (pinfunction "WSO_1") (pintype "output+no_connect"))
    )
    (net (code "65") (name "unconnected-(MK2-SCK-Pad6)") (class "Default")
      (node (ref "MK2") (pin "6") (pinfunction "SCK_6") (pintype "input"))
    )
    (net (code "66") (name "unconnected-(MK2-WS-Pad5)") (class "Default")
      (node (ref "MK2") (pin "5") (pinfunction "WS_5") (pintype "input"))
    )
    (net (code "67") (name "unconnected-(MK2-WSO-Pad1)") (class "Default")
      (node (ref "MK2") (pin "1") (pinfunction "WSO_1") (pintype "output+no_connect"))
    )
    (net (code "68") (name "unconnected-(MK3-SCK-Pad6)") (class "Default")
      (node (ref "MK3") (pin "6") (pinfunction "SCK_6") (pintype "input"))
    )
    (net (code "69") (name "unconnected-(MK3-WS-Pad5)") (class "Default")
      (node (ref "MK3") (pin "5") (pinfunction "WS_5") (pintype "input"))
    )
    (net (code "70") (name "unconnected-(MK3-WSO-Pad1)") (class "Default")
      (node (ref "MK3") (pin "1") (pinfunction "WSO_1") (pintype "output+no_connect"))
    )
    (net (code "71") (name "unconnected-(MK4-SCK-Pad6)") (class "Default")
      (node (ref "MK4") (pin "6") (pinfunction "SCK_6") (pintype "input"))
    )
    (net (code "72") (name "unconnected-(MK4-WS-Pad5)") (class "Default")
      (node (ref "MK4") (pin "5") (pinfunction "WS_5") (pintype "input"))
    )
    (net (code "73") (name "unconnected-(MK4-WSO-Pad1)") (class "Default")
      (node (ref "MK4") (pin "1") (pinfunction "WSO_1") (pintype "output+no_connect"))
    )
    (net (code "74") (name "unconnected-(MK5-SCK-Pad6)") (class "Default")
      (node (ref "MK5") (pin "6") (pinfunction "SCK_6") (pintype "input"))
    )
    (net (code "75") (name "unconnected-(MK5-WS-Pad5)") (class "Default")
      (node (ref "MK5") (pin "5") (pinfunction "WS_5") (pintype "input"))
    )
    (net (code "76") (name "unconnected-(MK5-WSO-Pad1)") (class "Default")
      (node (ref "MK5") (pin "1") (pinfunction "WSO_1") (pintype "output+no_connect"))
    )
    (net (code "77") (name "unconnected-(MK6-SCK-Pad6)") (class "Default")
      (node (ref "MK6") (pin "6") (pinfunction "SCK_6") (pintype "input"))
    )
    (net (code "78") (name "unconnected-(MK6-WS-Pad5)") (class "Default")
      (node (ref "MK6") (pin "5") (pinfunction "WS_5") (pintype "input"))
    )
    (net (code "79") (name "unconnected-(MK6-WSO-Pad1)") (class "Default")
      (node (ref "MK6") (pin "1") (pinfunction "WSO_1") (pintype "output+no_connect"))
    )
    (net (code "80") (name "unconnected-(MK7-SCK-Pad6)") (class "Default")
      (node (ref "MK7") (pin "6") (pinfunction "SCK_6") (pintype "input"))
    )
    (net (code "81") (name "unconnected-(MK7-WS-Pad5)") (class "Default")
      (node (ref "MK7") (pin "5") (pinfunction "WS_5") (pintype "input"))
    )
    (net (code "82") (name "unconnected-(MK7-WSO-Pad1)") (class "Default")
      (node (ref "MK7") (pin "1") (pinfunction "WSO_1") (pintype "output+no_connect"))
    )
    (net (code "83") (name "unconnected-(MK8-SCK-Pad6)") (class "Default")
      (node (ref "MK8") (pin "6") (pinfunction "SCK_6") (pintype "input"))
    )
    (net (code "84") (name "unconnected-(MK8-WS-Pad5)") (class "Default")
      (node (ref "MK8") (pin "5") (pinfunction "WS_5") (pintype "input"))
    )
    (net (code "85") (name "unconnected-(MK8-WSO-Pad1)") (class "Default")
      (node (ref "MK8") (pin "1") (pinfunction "WSO_1") (pintype "output+no_connect"))
    )
    (net (code "86") (name "unconnected-(MK9-SCK-Pad6)") (class "Default")
      (node (ref "MK9") (pin "6") (pinfunction "SCK_6") (pintype "input"))
    )
    (net (code "87") (name "unconnected-(MK9-WS-Pad5)") (class "Default")
      (node (ref "MK9") (pin "5") (pinfunction "WS_5") (pintype "input"))
    )
    (net (code "88") (name "unconnected-(MK9-WSO-Pad1)") (class "Default")
      (node (ref "MK9") (pin "1") (pinfunction "WSO_1") (pintype "output+no_connect"))
    )
    (net (code "89") (name "unconnected-(MK10-SCK-Pad6)") (class "Default")
      (node (ref "MK10") (pin "6") (pinfunction "SCK_6") (pintype "input"))
    )
    (net (code "90") (name "unconnected-(MK10-WS-Pad5)") (class "Default")
      (node (ref "MK10") (pin "5") (pinfunction "WS_5") (pintype "input"))
    )
    (net (code "91") (name "unconnected-(MK10-WSO-Pad1)") (class "Default")
      (node (ref "MK10") (pin "1") (pinfunction "WSO_1") (pintype "output+no_connect"))
    )
    (net (code "92") (name "unconnected-(MK11-SCK-Pad6)") (class "Default")
      (node (ref "MK11") (pin "6") (pinfunction "SCK_6") (pintype "input"))
    )
    (net (code "93") (name "unconnected-(MK11-WS-Pad5)") (class "Default")
      (node (ref "MK11") (pin "5") (pinfunction "WS_5") (pintype "input"))
    )
    (net (code "94") (name "unconnected-(MK11-WSO-Pad1)") (class "Default")
      (node (ref "MK11") (pin "1") (pinfunction "WSO_1") (pintype "output+no_connect"))
    )
    (net (code "95") (name "unconnected-(MK12-SCK-Pad6)") (class "Default")
      (node (ref "MK12") (pin "6") (pinfunction "SCK_6") (pintype "input"))
    )
    (net (code "96") (name "unconnected-(MK12-WS-Pad5)") (class "Default")
      (node (ref "MK12") (pin "5") (pinfunction "WS_5") (pintype "input"))
    )
    (net (code "97") (name "unconnected-(MK12-WSO-Pad1)") (class "Default")
      (node (ref "MK12") (pin "1") (pinfunction "WSO_1") (pintype "output+no_connect"))
    )
    (net (code "98") (name "unconnected-(MK13-SCK-Pad6)") (class "Default")
      (node (ref "MK13") (pin "6") (pinfunction "SCK_6") (pintype "input"))
    )
    (net (code "99") (name "unconnected-(MK13-WS-Pad5)") (class "Default")
      (node (ref "MK13") (pin "5") (pinfunction "WS_5") (pintype "input"))
    )
    (net (code "100") (name "unconnected-(MK13-WSO-Pad1)") (class "Default")
      (node (ref "MK13") (pin "1") (pinfunction "WSO_1") (pintype "output+no_connect"))
    )
    (net (code "101") (name "unconnected-(MK14-SCK-Pad6)") (class "Default")
      (node (ref "MK14") (pin "6") (pinfunction "SCK_6") (pintype "input"))
    )
    (net (code "102") (name "unconnected-(MK14-WS-Pad5)") (class "Default")
      (node (ref "MK14") (pin "5") (pinfunction "WS_5") (pintype "input"))
    )
    (net (code "103") (name "unconnected-(MK14-WSO-Pad1)") (class "Default")
      (node (ref "MK14") (pin "1") (pinfunction "WSO_1") (pintype "output+no_connect"))
    )
    (net (code "104") (name "unconnected-(MK15-SCK-Pad6)") (class "Default")
      (node (ref "MK15") (pin "6") (pinfunction "SCK_6") (pintype "input"))
    )
    (net (code "105") (name "unconnected-(MK15-WS-Pad5)") (class "Default")
      (node (ref "MK15") (pin "5") (pinfunction "WS_5") (pintype "input"))
    )
    (net (code "106") (name "unconnected-(MK15-WSO-Pad1)") (class "Default")
      (node (ref "MK15") (pin "1") (pinfunction "WSO_1") (pintype "output+no_connect"))
    )
    (net (code "107") (name "unconnected-(MK16-SCK-Pad6)") (class "Default")
      (node (ref "MK16") (pin "6") (pinfunction "SCK_6") (pintype "input"))
    )
    (net (code "108") (name "unconnected-(MK16-WS-Pad5)") (class "Default")
      (node (ref "MK16") (pin "5") (pinfunction "WS_5") (pintype "input"))
    )
    (net (code "109") (name "unconnected-(MK16-WSO-Pad1)") (class "Default")
      (node (ref "MK16") (pin "1") (pinfunction "WSO_1") (pintype "output+no_connect"))
    )
    (net (code "110") (name "unconnected-(R44-Pad1)") (class "Default")
      (node (ref "R44") (pin "1") (pinfunction "1_1") (pintype "passive"))
    )
    (net (code "111") (name "unconnected-(R45-Pad1)") (class "Default")
      (node (ref "R45") (pin "1") (pinfunction "1_1") (pintype "passive"))
    )
    (net (code "112") (name "unconnected-(R46-Pad1)") (class "Default")
      (node (ref "R46") (pin "1") (pinfunction "1_1") (pintype "passive"))
    )
    (net (code "113") (name "unconnected-(R47-Pad1)") (class "Default")
      (node (ref "R47") (pin "1") (pinfunction "1_1") (pintype "passive"))
    )
    (net (code "114") (name "unconnected-(R48-Pad1)") (class "Default")
      (node (ref "R48") (pin "1") (pinfunction "1_1") (pintype "passive"))
    )
    (net (code "115") (name "unconnected-(R49-Pad1)") (class "Default")
      (node (ref "R49") (pin "1") (pinfunction "1_1") (pintype "passive"))
    )
    (net (code "116") (name "unconnected-(R50-Pad1)") (class "Default")
      (node (ref "R50") (pin "1") (pinfunction "1_1") (pintype "passive"))
    )
    (net (code "117") (name "unconnected-(R51-Pad1)") (class "Default")
      (node (ref "R51") (pin "1") (pinfunction "1_1") (pintype "passive"))
    )
    (net (code "118") (name "unconnected-(R52-Pad1)") (class "Default")
      (node (ref "R52") (pin "1") (pinfunction "1_1") (pintype "passive"))
    )
    (net (code "119") (name "unconnected-(R54-Pad1)") (class "Default")
      (node (ref "R54") (pin "1") (pinfunction "1_1") (pintype "passive"))
    )
    (net (code "120") (name "unconnected-(R55-Pad1)") (class "Default")
      (node (ref "R55") (pin "1") (pinfunction "1_1") (pintype "passive"))
    )
    (net (code "121") (name "unconnected-(R56-Pad1)") (class "Default")
      (node (ref "R56") (pin "1") (pinfunction "1_1") (pintype "passive"))
    )
    (net (code "122") (name "unconnected-(R57-Pad1)") (class "Default")
      (node (ref "R57") (pin "1") (pinfunction "1_1") (pintype "passive"))
    )
    (net (code "123") (name "unconnected-(R58-Pad1)") (class "Default")
      (node (ref "R58") (pin "1") (pinfunction "1_1") (pintype "passive"))
    )
    (net (code "124") (name "unconnected-(R59-Pad1)") (class "Default")
      (node (ref "R59") (pin "1") (pinfunction "1_1") (pintype "passive"))
    )
    (net (code "125") (name "unconnected-(R60-Pad1)") (class "Default")
      (node (ref "R60") (pin "1") (pinfunction "1_1") (pintype "passive"))
    )
  )
)
